# ProPrj_GlowPolyDriver_2025-09-27.net
KiCad netlist of a schematic drawn in EasyEDA Pro
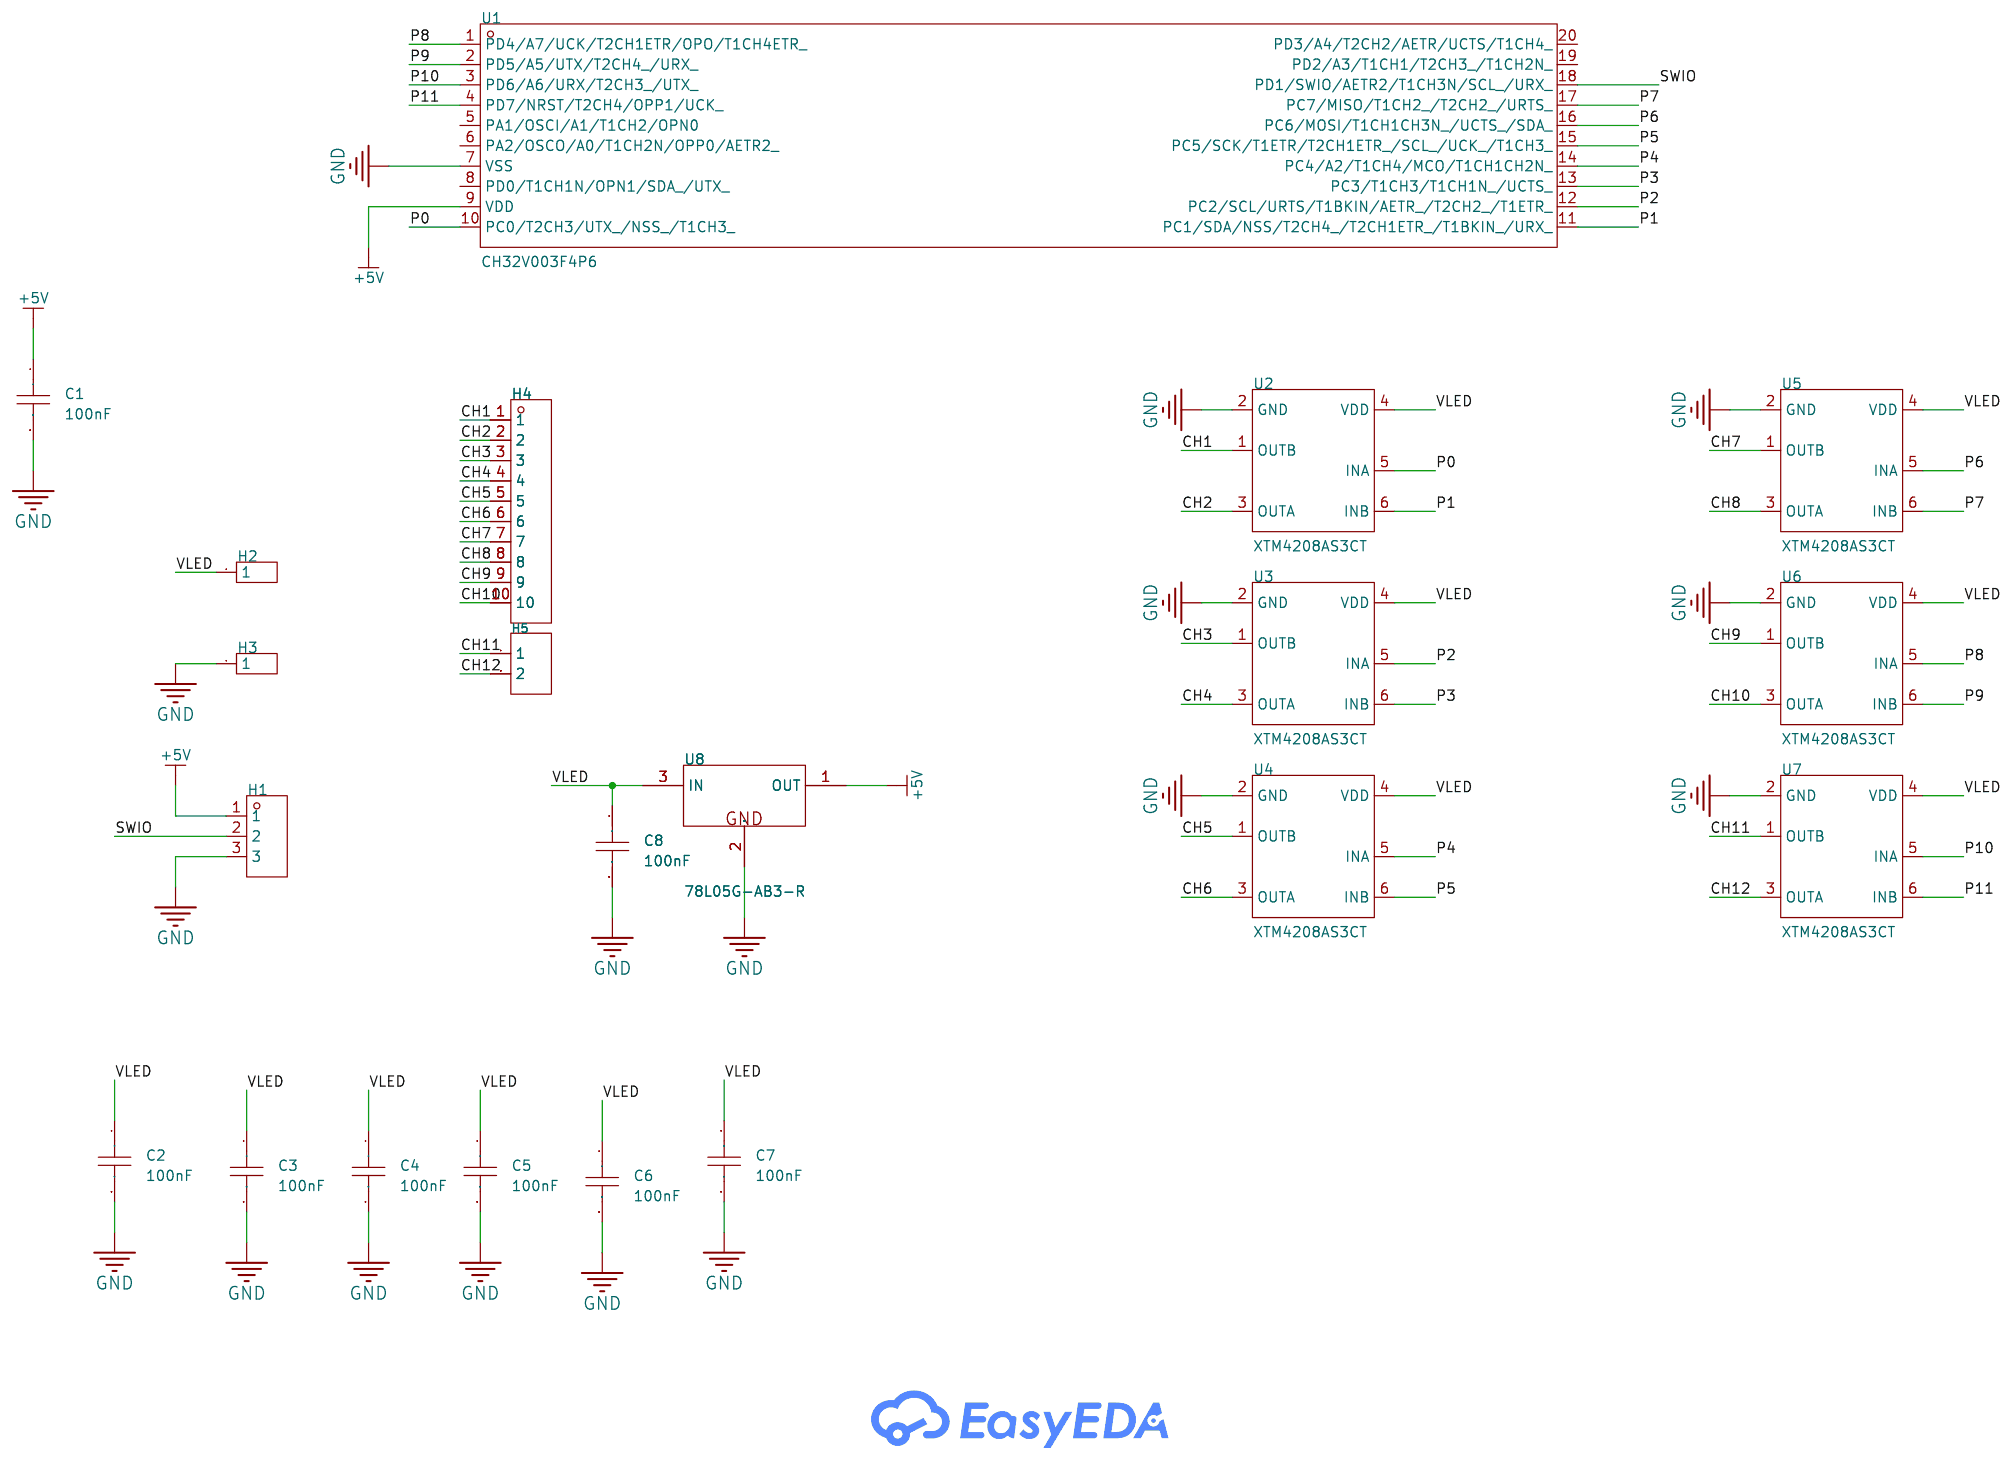
[diagram p0: schematic sheet]

(export (version "E")
  (design (tool "Eeschema 10.0.6"))
  (components
    (comp (ref "C1")
      (value "100nF")
      (footprint "easyedapro:C0603")
      (libsource (lib "easyedapro") (part "CAP"))
    )
    (comp (ref "C2")
      (value "100nF")
      (footprint "easyedapro:C0603")
      (libsource (lib "easyedapro") (part "CAP"))
    )
    (comp (ref "C3")
      (value "100nF")
      (footprint "easyedapro:C0603")
      (libsource (lib "easyedapro") (part "CAP"))
    )
    (comp (ref "C4")
      (value "100nF")
      (footprint "easyedapro:C0603")
      (libsource (lib "easyedapro") (part "CAP"))
    )
    (comp (ref "C5")
      (value "100nF")
      (footprint "easyedapro:C0603")
      (libsource (lib "easyedapro") (part "CAP"))
    )
    (comp (ref "C6")
      (value "100nF")
      (footprint "easyedapro:C0603")
      (libsource (lib "easyedapro") (part "CAP"))
    )
    (comp (ref "C7")
      (value "100nF")
      (footprint "easyedapro:C0603")
      (libsource (lib "easyedapro") (part "CAP"))
    )
    (comp (ref "C8")
      (value "100nF")
      (footprint "easyedapro:C0603")
      (libsource (lib "easyedapro") (part "CAP"))
    )
    (comp (ref "H1")
      (value "~")
      (footprint "easyedapro:HDR-TH_3P-P2.54-V-F")
      (libsource (lib "easyedapro") (part "PM254V-11-03-H85"))
    )
    (comp (ref "H2")
      (value "~")
      (footprint "easyedapro:HDR-TH_1P-V-M_XKB_X4611WV-01I-C28D40")
      (libsource (lib "easyedapro") (part "HDR_1x1"))
    )
    (comp (ref "H3")
      (value "~")
      (footprint "easyedapro:HDR-TH_1P-V-M_XKB_X4611WV-01I-C28D40")
      (libsource (lib "easyedapro") (part "HDR_1x1"))
    )
    (comp (ref "H4")
      (value "~")
      (footprint "easyedapro:HDR-TH_10P-P2.54-V-F")
      (libsource (lib "easyedapro") (part "X5511FV-10-C70D30-1000"))
    )
    (comp (ref "H5")
      (value "~")
      (footprint "easyedapro:HDR-TH_2P-P2.54-V-F")
      (libsource (lib "easyedapro") (part "Header-Female-2.54_1x2"))
    )
    (comp (ref "U1")
      (value "CH32V003F4P6")
      (footprint "easyedapro:TSSOP-20_L6.5-W4.4-P0.65-LS6.4-BL")
      (fields (field (name "Manufacturer") "WCH(南京沁恒)"))
      (libsource (lib "easyedapro") (part "CH32V003F4P6"))
    )
    (comp (ref "U2")
      (value "XTM4208AS3CT")
      (footprint "easyedapro:SOT-23-6_L2.9-W1.6-P0.95-LS2.8-BR")
      (fields (field (name "Manufacturer") "XTX(芯天下)"))
      (libsource (lib "easyedapro") (part "XTM4208AS3CT"))
    )
    (comp (ref "U3")
      (value "XTM4208AS3CT")
      (footprint "easyedapro:SOT-23-6_L2.9-W1.6-P0.95-LS2.8-BR")
      (fields (field (name "Manufacturer") "XTX(芯天下)"))
      (libsource (lib "easyedapro") (part "XTM4208AS3CT"))
    )
    (comp (ref "U4")
      (value "XTM4208AS3CT")
      (footprint "easyedapro:SOT-23-6_L2.9-W1.6-P0.95-LS2.8-BR")
      (fields (field (name "Manufacturer") "XTX(芯天下)"))
      (libsource (lib "easyedapro") (part "XTM4208AS3CT"))
    )
    (comp (ref "U5")
      (value "XTM4208AS3CT")
      (footprint "easyedapro:SOT-23-6_L2.9-W1.6-P0.95-LS2.8-BR")
      (fields (field (name "Manufacturer") "XTX(芯天下)"))
      (libsource (lib "easyedapro") (part "XTM4208AS3CT"))
    )
    (comp (ref "U6")
      (value "XTM4208AS3CT")
      (footprint "easyedapro:SOT-23-6_L2.9-W1.6-P0.95-LS2.8-BR")
      (fields (field (name "Manufacturer") "XTX(芯天下)"))
      (libsource (lib "easyedapro") (part "XTM4208AS3CT"))
    )
    (comp (ref "U7")
      (value "XTM4208AS3CT")
      (footprint "easyedapro:SOT-23-6_L2.9-W1.6-P0.95-LS2.8-BR")
      (fields (field (name "Manufacturer") "XTX(芯天下)"))
      (libsource (lib "easyedapro") (part "XTM4208AS3CT"))
    )
    (comp (ref "U8")
      (value "78L05G-AB3-R")
      (footprint "easyedapro:SOT-89-3_L4.5-W2.5-P1.50-LS4.2-BR")
      (fields (field (name "Manufacturer") "UTC(友顺)"))
      (libsource (lib "easyedapro") (part "78L05G-AB3-R"))
    )
  )
  (nets
    (net (code "1") (name "+5V") (class "Default")
      (node (ref "C1") (pin "1") (pinfunction "1_1") (pintype "input"))
      (node (ref "H1") (pin "1") (pinfunction "1_1") (pintype "unspecified"))
      (node (ref "U1") (pin "9") (pinfunction "VDD_9") (pintype "unspecified"))
      (node (ref "U8") (pin "1") (pinfunction "OUT_1") (pintype "unspecified"))
    )
    (net (code "2") (name "/CH1") (class "Default")
      (node (ref "H4") (pin "1") (pinfunction "1_1") (pintype "unspecified"))
      (node (ref "U2") (pin "1") (pinfunction "OUTB_1") (pintype "unspecified"))
    )
    (net (code "3") (name "/CH2") (class "Default")
      (node (ref "H4") (pin "2") (pinfunction "2_2") (pintype "unspecified"))
      (node (ref "U2") (pin "3") (pinfunction "OUTA_3") (pintype "unspecified"))
    )
    (net (code "4") (name "/CH3") (class "Default")
      (node (ref "H4") (pin "3") (pinfunction "3_3") (pintype "unspecified"))
      (node (ref "U3") (pin "1") (pinfunction "OUTB_1") (pintype "unspecified"))
    )
    (net (code "5") (name "/CH4") (class "Default")
      (node (ref "H4") (pin "4") (pinfunction "4_4") (pintype "unspecified"))
      (node (ref "U3") (pin "3") (pinfunction "OUTA_3") (pintype "unspecified"))
    )
    (net (code "6") (name "/CH5") (class "Default")
      (node (ref "H4") (pin "5") (pinfunction "5_5") (pintype "unspecified"))
      (node (ref "U4") (pin "1") (pinfunction "OUTB_1") (pintype "unspecified"))
    )
    (net (code "7") (name "/CH6") (class "Default")
      (node (ref "H4") (pin "6") (pinfunction "6_6") (pintype "unspecified"))
      (node (ref "U4") (pin "3") (pinfunction "OUTA_3") (pintype "unspecified"))
    )
    (net (code "8") (name "/CH7") (class "Default")
      (node (ref "H4") (pin "7") (pinfunction "7_7") (pintype "unspecified"))
      (node (ref "U5") (pin "1") (pinfunction "OUTB_1") (pintype "unspecified"))
    )
    (net (code "9") (name "/CH8") (class "Default")
      (node (ref "H4") (pin "8") (pinfunction "8_8") (pintype "unspecified"))
      (node (ref "U5") (pin "3") (pinfunction "OUTA_3") (pintype "unspecified"))
    )
    (net (code "10") (name "/CH9") (class "Default")
      (node (ref "H4") (pin "9") (pinfunction "9_9") (pintype "unspecified"))
      (node (ref "U6") (pin "1") (pinfunction "OUTB_1") (pintype "unspecified"))
    )
    (net (code "11") (name "/CH10") (class "Default")
      (node (ref "H4") (pin "10") (pinfunction "10_10") (pintype "unspecified"))
      (node (ref "U6") (pin "3") (pinfunction "OUTA_3") (pintype "unspecified"))
    )
    (net (code "12") (name "/CH11") (class "Default")
      (node (ref "H5") (pin "1") (pinfunction "1_1") (pintype "input"))
      (node (ref "U7") (pin "1") (pinfunction "OUTB_1") (pintype "unspecified"))
    )
    (net (code "13") (name "/CH12") (class "Default")
      (node (ref "H5") (pin "2") (pinfunction "2_2") (pintype "input"))
      (node (ref "U7") (pin "3") (pinfunction "OUTA_3") (pintype "unspecified"))
    )
    (net (code "14") (name "/P0") (class "Default")
      (node (ref "U1") (pin "10") (pinfunction "PC0/T2CH3/UTX_/NSS_/T1CH3__10") (pintype "unspecified"))
      (node (ref "U2") (pin "5") (pinfunction "INA_5") (pintype "unspecified"))
    )
    (net (code "15") (name "/P1") (class "Default")
      (node (ref "U1") (pin "11") (pinfunction "PC1/SDA/NSS/T2CH4_/T2CH1ETR_/T1BKIN_/URX__11") (pintype "unspecified"))
      (node (ref "U2") (pin "6") (pinfunction "INB_6") (pintype "unspecified"))
    )
    (net (code "16") (name "/P2") (class "Default")
      (node (ref "U1") (pin "12") (pinfunction "PC2/SCL/URTS/T1BKIN/AETR_/T2CH2_/T1ETR__12") (pintype "unspecified"))
      (node (ref "U3") (pin "5") (pinfunction "INA_5") (pintype "unspecified"))
    )
    (net (code "17") (name "/P3") (class "Default")
      (node (ref "U1") (pin "13") (pinfunction "PC3/T1CH3/T1CH1N_/UCTS__13") (pintype "unspecified"))
      (node (ref "U3") (pin "6") (pinfunction "INB_6") (pintype "unspecified"))
    )
    (net (code "18") (name "/P4") (class "Default")
      (node (ref "U1") (pin "14") (pinfunction "PC4/A2/T1CH4/MCO/T1CH1CH2N__14") (pintype "unspecified"))
      (node (ref "U4") (pin "5") (pinfunction "INA_5") (pintype "unspecified"))
    )
    (net (code "19") (name "/P5") (class "Default")
      (node (ref "U1") (pin "15") (pinfunction "PC5/SCK/T1ETR/T2CH1ETR_/SCL_/UCK_/T1CH3__15") (pintype "unspecified"))
      (node (ref "U4") (pin "6") (pinfunction "INB_6") (pintype "unspecified"))
    )
    (net (code "20") (name "/P6") (class "Default")
      (node (ref "U1") (pin "16") (pinfunction "PC6/MOSI/T1CH1CH3N_/UCTS_/SDA__16") (pintype "unspecified"))
      (node (ref "U5") (pin "5") (pinfunction "INA_5") (pintype "unspecified"))
    )
    (net (code "21") (name "/P7") (class "Default")
      (node (ref "U1") (pin "17") (pinfunction "PC7/MISO/T1CH2_/T2CH2_/URTS__17") (pintype "unspecified"))
      (node (ref "U5") (pin "6") (pinfunction "INB_6") (pintype "unspecified"))
    )
    (net (code "22") (name "/P8") (class "Default")
      (node (ref "U1") (pin "1") (pinfunction "PD4/A7/UCK/T2CH1ETR/OPO/T1CH4ETR__1") (pintype "unspecified"))
      (node (ref "U6") (pin "5") (pinfunction "INA_5") (pintype "unspecified"))
    )
    (net (code "23") (name "/P9") (class "Default")
      (node (ref "U1") (pin "2") (pinfunction "PD5/A5/UTX/T2CH4_/URX__2") (pintype "unspecified"))
      (node (ref "U6") (pin "6") (pinfunction "INB_6") (pintype "unspecified"))
    )
    (net (code "24") (name "/P10") (class "Default")
      (node (ref "U1") (pin "3") (pinfunction "PD6/A6/URX/T2CH3_/UTX__3") (pintype "unspecified"))
      (node (ref "U7") (pin "5") (pinfunction "INA_5") (pintype "unspecified"))
    )
    (net (code "25") (name "/P11") (class "Default")
      (node (ref "U1") (pin "4") (pinfunction "PD7/NRST/T2CH4/OPP1/UCK__4") (pintype "unspecified"))
      (node (ref "U7") (pin "6") (pinfunction "INB_6") (pintype "unspecified"))
    )
    (net (code "26") (name "/SWIO") (class "Default")
      (node (ref "H1") (pin "2") (pinfunction "2_2") (pintype "unspecified"))
      (node (ref "U1") (pin "18") (pinfunction "PD1/SWIO/AETR2/T1CH3N/SCL_/URX__18") (pintype "unspecified"))
    )
    (net (code "27") (name "/VLED") (class "Default")
      (node (ref "C2") (pin "1") (pinfunction "1_1") (pintype "input"))
      (node (ref "C3") (pin "1") (pinfunction "1_1") (pintype "input"))
      (node (ref "C4") (pin "1") (pinfunction "1_1") (pintype "input"))
      (node (ref "C5") (pin "1") (pinfunction "1_1") (pintype "input"))
      (node (ref "C6") (pin "1") (pinfunction "1_1") (pintype "input"))
      (node (ref "C7") (pin "1") (pinfunction "1_1") (pintype "input"))
      (node (ref "C8") (pin "1") (pinfunction "1_1") (pintype "input"))
      (node (ref "H2") (pin "1") (pinfunction "1_1") (pintype "unspecified"))
      (node (ref "U2") (pin "4") (pinfunction "VDD_4") (pintype "unspecified"))
      (node (ref "U3") (pin "4") (pinfunction "VDD_4") (pintype "unspecified"))
      (node (ref "U4") (pin "4") (pinfunction "VDD_4") (pintype "unspecified"))
      (node (ref "U5") (pin "4") (pinfunction "VDD_4") (pintype "unspecified"))
      (node (ref "U6") (pin "4") (pinfunction "VDD_4") (pintype "unspecified"))
      (node (ref "U7") (pin "4") (pinfunction "VDD_4") (pintype "unspecified"))
      (node (ref "U8") (pin "3") (pinfunction "IN_3") (pintype "unspecified"))
    )
    (net (code "28") (name "GND") (class "Default")
      (node (ref "C1") (pin "2") (pinfunction "2_2") (pintype "input"))
      (node (ref "C2") (pin "2") (pinfunction "2_2") (pintype "input"))
      (node (ref "C3") (pin "2") (pinfunction "2_2") (pintype "input"))
      (node (ref "C4") (pin "2") (pinfunction "2_2") (pintype "input"))
      (node (ref "C5") (pin "2") (pinfunction "2_2") (pintype "input"))
      (node (ref "C6") (pin "2") (pinfunction "2_2") (pintype "input"))
      (node (ref "C7") (pin "2") (pinfunction "2_2") (pintype "input"))
      (node (ref "C8") (pin "2") (pinfunction "2_2") (pintype "input"))
      (node (ref "H1") (pin "3") (pinfunction "3_3") (pintype "unspecified"))
      (node (ref "H3") (pin "1") (pinfunction "1_1") (pintype "unspecified"))
      (node (ref "U1") (pin "7") (pinfunction "VSS_7") (pintype "unspecified"))
      (node (ref "U2") (pin "2") (pinfunction "GND_2") (pintype "unspecified"))
      (node (ref "U3") (pin "2") (pinfunction "GND_2") (pintype "unspecified"))
      (node (ref "U4") (pin "2") (pinfunction "GND_2") (pintype "unspecified"))
      (node (ref "U5") (pin "2") (pinfunction "GND_2") (pintype "unspecified"))
      (node (ref "U6") (pin "2") (pinfunction "GND_2") (pintype "unspecified"))
      (node (ref "U7") (pin "2") (pinfunction "GND_2") (pintype "unspecified"))
      (node (ref "U8") (pin "2") (pinfunction "GND_2") (pintype "unspecified"))
    )
    (net (code "29") (name "unconnected-(U1-PA1{slash}OSCI{slash}A1{slash}T1CH2{slash}OPN0-Pad5)") (class "Default")
      (node (ref "U1") (pin "5") (pinfunction "PA1/OSCI/A1/T1CH2/OPN0_5") (pintype "unspecified"))
    )
    (net (code "30") (name "unconnected-(U1-PA2{slash}OSCO{slash}A0{slash}T1CH2N{slash}OPP0{slash}AETR2_-Pad6)") (class "Default")
      (node (ref "U1") (pin "6") (pinfunction "PA2/OSCO/A0/T1CH2N/OPP0/AETR2__6") (pintype "unspecified"))
    )
    (net (code "31") (name "unconnected-(U1-PD0{slash}T1CH1N{slash}OPN1{slash}SDA_{slash}UTX_-Pad8)") (class "Default")
      (node (ref "U1") (pin "8") (pinfunction "PD0/T1CH1N/OPN1/SDA_/UTX__8") (pintype "unspecified"))
    )
    (net (code "32") (name "unconnected-(U1-PD2{slash}A3{slash}T1CH1{slash}T2CH3_{slash}T1CH2N_-Pad19)") (class "Default")
      (node (ref "U1") (pin "19") (pinfunction "PD2/A3/T1CH1/T2CH3_/T1CH2N__19") (pintype "unspecified"))
    )
    (net (code "33") (name "unconnected-(U1-PD3{slash}A4{slash}T2CH2{slash}AETR{slash}UCTS{slash}T1CH4_-Pad20)") (class "Default")
      (node (ref "U1") (pin "20") (pinfunction "PD3/A4/T2CH2/AETR/UCTS/T1CH4__20") (pintype "unspecified"))
    )
  )
)
